# sch_cm4_sd_card.net
KiCad netlist of a schematic drawn in Altium Designer
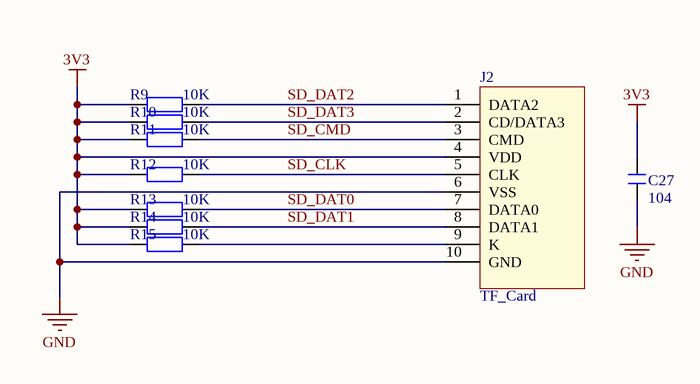
[diagram p0: sch_cm4_sd_card.SchDoc]

(export (version "E")
  (design (tool "Eeschema 10.0.6"))
  (components
    (comp (ref "C27")
      (value "104")
      (footprint "C 0402_L")
      (description "贴片电容")
      (libsource (lib "0.1 - 电阻-电容-电感") (part "C"))
    )
    (comp (ref "J2")
      (value "TF_Card")
      (footprint "Micro SD")
      (description "TF卡座")
      (libsource (lib "0.8 - 以太网-音频-USB插座") (part "TF_Card"))
    )
    (comp (ref "R9")
      (value "10K")
      (footprint "R 0402_L")
      (description "贴片电阻")
      (fields (field (name "版权归属") "来自淘宝 ID：黄晶宝石"))
      (libsource (lib "0.1 - 电阻-电容-电感") (part "R"))
    )
    (comp (ref "R10")
      (value "10K")
      (footprint "R 0402_L")
      (description "贴片电阻")
      (fields (field (name "版权归属") "来自淘宝 ID：黄晶宝石"))
      (libsource (lib "0.1 - 电阻-电容-电感") (part "R"))
    )
    (comp (ref "R11")
      (value "10K")
      (footprint "R 0402_L")
      (description "贴片电阻")
      (fields (field (name "版权归属") "来自淘宝 ID：黄晶宝石"))
      (libsource (lib "0.1 - 电阻-电容-电感") (part "R"))
    )
    (comp (ref "R12")
      (value "10K")
      (footprint "R 0402_L")
      (description "贴片电阻")
      (fields (field (name "版权归属") "来自淘宝 ID：黄晶宝石"))
      (libsource (lib "0.1 - 电阻-电容-电感") (part "R"))
    )
    (comp (ref "R13")
      (value "10K")
      (footprint "R 0402_L")
      (description "贴片电阻")
      (fields (field (name "版权归属") "来自淘宝 ID：黄晶宝石"))
      (libsource (lib "0.1 - 电阻-电容-电感") (part "R"))
    )
    (comp (ref "R14")
      (value "10K")
      (footprint "R 0402_L")
      (description "贴片电阻")
      (fields (field (name "版权归属") "来自淘宝 ID：黄晶宝石"))
      (libsource (lib "0.1 - 电阻-电容-电感") (part "R"))
    )
    (comp (ref "R15")
      (value "10K")
      (footprint "R 0402_L")
      (description "贴片电阻")
      (fields (field (name "版权归属") "来自淘宝 ID：黄晶宝石"))
      (libsource (lib "0.1 - 电阻-电容-电感") (part "R"))
    )
  )
  (nets
    (net (code "1") (name "/SD_CLK") (class "Default")
      (node (ref "J2") (pin "5") (pinfunction "CLK_5") (pintype "passive"))
      (node (ref "R12") (pin "2") (pinfunction "2_2") (pintype "passive"))
    )
    (net (code "2") (name "/SD_CMD") (class "Default")
      (node (ref "J2") (pin "3") (pinfunction "CMD_3") (pintype "passive"))
      (node (ref "R11") (pin "2") (pinfunction "2_2") (pintype "passive"))
    )
    (net (code "3") (name "/SD_DAT0") (class "Default")
      (node (ref "J2") (pin "7") (pinfunction "DATA0_7") (pintype "passive"))
      (node (ref "R13") (pin "2") (pinfunction "2_2") (pintype "passive"))
    )
    (net (code "4") (name "/SD_DAT1") (class "Default")
      (node (ref "J2") (pin "8") (pinfunction "DATA1_8") (pintype "passive"))
      (node (ref "R14") (pin "2") (pinfunction "2_2") (pintype "passive"))
    )
    (net (code "5") (name "/SD_DAT2") (class "Default")
      (node (ref "J2") (pin "1") (pinfunction "DATA2_1") (pintype "passive"))
      (node (ref "R9") (pin "2") (pinfunction "2_2") (pintype "passive"))
    )
    (net (code "6") (name "/SD_DAT3") (class "Default")
      (node (ref "J2") (pin "2") (pinfunction "CD/DATA3_2") (pintype "passive"))
      (node (ref "R10") (pin "2") (pinfunction "2_2") (pintype "passive"))
    )
    (net (code "7") (name "3V3") (class "Default")
      (node (ref "C27") (pin "2") (pinfunction "2_2") (pintype "passive"))
      (node (ref "J2") (pin "4") (pinfunction "VDD_4") (pintype "passive"))
      (node (ref "R10") (pin "1") (pinfunction "1_1") (pintype "passive"))
      (node (ref "R11") (pin "1") (pinfunction "1_1") (pintype "passive"))
      (node (ref "R12") (pin "1") (pinfunction "1_1") (pintype "passive"))
      (node (ref "R13") (pin "1") (pinfunction "1_1") (pintype "passive"))
      (node (ref "R14") (pin "1") (pinfunction "1_1") (pintype "passive"))
      (node (ref "R15") (pin "1") (pinfunction "1_1") (pintype "passive"))
      (node (ref "R9") (pin "1") (pinfunction "1_1") (pintype "passive"))
    )
    (net (code "8") (name "GND") (class "Default")
      (node (ref "C27") (pin "1") (pinfunction "1_1") (pintype "passive"))
      (node (ref "J2") (pin "10") (pinfunction "GND_10") (pintype "passive"))
      (node (ref "J2") (pin "6") (pinfunction "VSS_6") (pintype "passive"))
    )
    (net (code "9") (name "Net-(J2-K)") (class "Default")
      (node (ref "J2") (pin "9") (pinfunction "K_9") (pintype "passive"))
      (node (ref "R15") (pin "2") (pinfunction "2_2") (pintype "passive"))
    )
  )
)
